# MCU_G0.net
KiCad netlist of a schematic drawn in Altium Designer
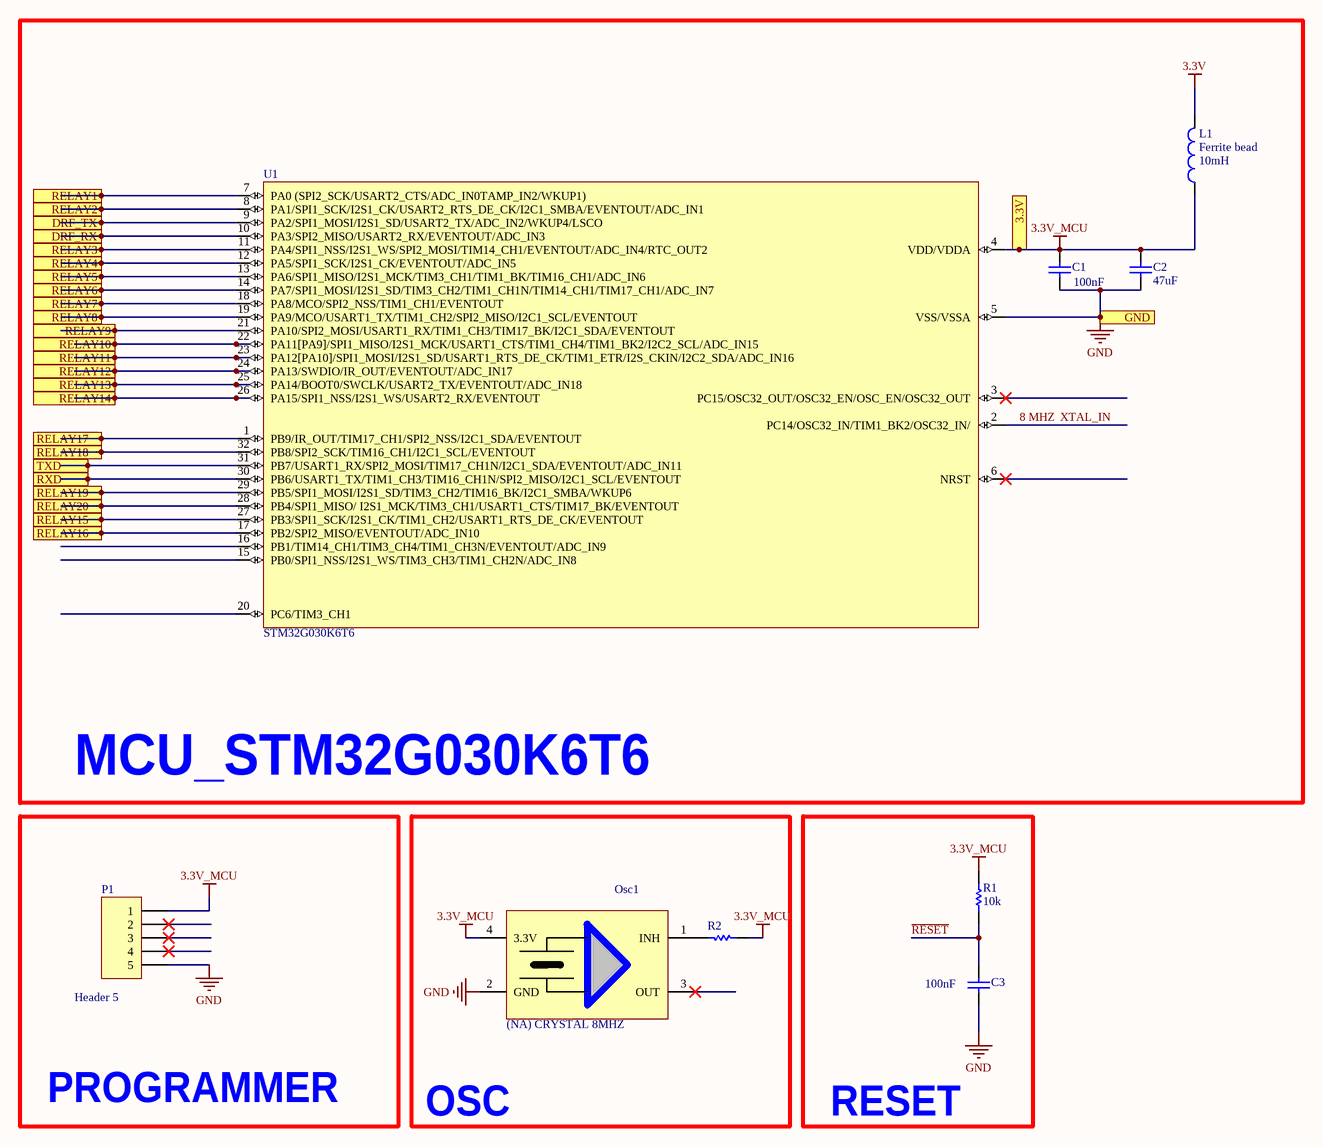
[diagram p0: MCU_G0.SchDoc]

(export (version "E")
  (design (tool "Eeschema 10.0.6"))
  (components
    (comp (ref "C1")
      (value "100nF")
      (footprint "0603 - RESISTOR")
      (description "Capacitor")
      (fields (field (name "PUBLISHER") "Altium Limited"))
      (libsource (lib "Miscellaneous Devices") (part "Cap"))
    )
    (comp (ref "C2")
      (value "47uF")
      (footprint "0603 - RESISTOR")
      (description "Capacitor")
      (fields (field (name "PUBLISHER") "Altium Limited"))
      (libsource (lib "Miscellaneous Devices") (part "Cap"))
    )
    (comp (ref "C3")
      (value "100nF")
      (footprint "0603 - RESISTOR")
      (description "Capacitor")
      (fields (field (name "PUBLISHER") "Altium Limited"))
      (libsource (lib "Miscellaneous Devices") (part "Cap"))
    )
    (comp (ref "L1")
      (value "Ferrite bead")
      (footprint "0603 - RESISTOR")
      (description "Inductor")
      (fields (field (name "ALTIUM_VALUE") "10mH") (field (name "PUBLISHER") "Altium Limited"))
      (libsource (lib "Miscellaneous Devices") (part "Inductor"))
    )
    (comp (ref "Osc1")
      (value "(NA) CRYSTAL 8MHZ")
      (footprint "XTAL_5X7")
      (libsource (lib "New Lib") (part "OSILATOR"))
    )
    (comp (ref "P1")
      (value "Header 5")
      (footprint "HDR1X5_2mm_small")
      (description "Header, 5-Pin")
      (fields (field (name "PUBLISHER") "Altium Limited"))
      (libsource (lib "Miscellaneous Connectors") (part "Header 5"))
    )
    (comp (ref "R1")
      (value "10k")
      (footprint "0603 - RESISTOR")
      (description "Resistor")
      (fields (field (name "PUBLISHER") "Altium Limited"))
      (libsource (lib "Miscellaneous Devices") (part "Res1"))
    )
    (comp (ref "R2")
      (value "(NA)10k")
      (footprint "0603 - RESISTOR")
      (description "Resistor")
      (fields (field (name "PUBLISHER") "Altium Limited"))
      (libsource (lib "Miscellaneous Devices") (part "Res1"))
    )
    (comp (ref "U1")
      (value "STM32G030K6T6")
      (footprint "LQFP32")
      (description "ARMÂ® CortexÂ®-M0+ STM32G0 Microcontroller IC 32-Bit 64MHz 32KB (32K x 8) FLASH 32-LQFP (7x7)")
      (fields (field (name "MF") "STMicroelectronics"))
      (libsource (lib "Schlib1") (part "STM32G030K6T6"))
    )
  )
  (nets
    (net (code "1") (name "/8 MHZ") (class "Default")
      (node (ref "U1") (pin "2") (pinfunction "PC14/OSC32_IN/TIM1_BK2/OSC32_IN/_2") (pintype "bidirectional"))
    )
    (net (code "2") (name "/DRF_RX") (class "Default")
      (node (ref "U1") (pin "10") (pinfunction "PA3/SPI2_MISO/USART2_RX/EVENTOUT/ADC_IN3_10") (pintype "bidirectional"))
    )
    (net (code "3") (name "/DRF_TX") (class "Default")
      (node (ref "U1") (pin "9") (pinfunction "PA2/SPI1_MOSI/I2S1_SD/USART2_TX/ADC_IN2/WKUP4/LSCO_9") (pintype "bidirectional"))
    )
    (net (code "4") (name "/RELAY1") (class "Default")
      (node (ref "U1") (pin "7") (pinfunction "PA0_(SPI2_SCK/USART2_CTS/ADC_IN0TAMP_IN2/WKUP1)_7") (pintype "bidirectional"))
    )
    (net (code "5") (name "/RELAY2") (class "Default")
      (node (ref "U1") (pin "8") (pinfunction "PA1/SPI1_SCK/I2S1_CK/USART2_RTS_DE_CK/I2C1_SMBA/EVENTOUT/ADC_IN1_8") (pintype "bidirectional"))
    )
    (net (code "6") (name "/RELAY3") (class "Default")
      (node (ref "U1") (pin "11") (pinfunction "PA4/SPI1_NSS/I2S1_WS/SPI2_MOSI/TIM14_CH1/EVENTOUT/ADC_IN4/RTC_OUT2_11") (pintype "bidirectional"))
    )
    (net (code "7") (name "/RELAY4") (class "Default")
      (node (ref "U1") (pin "12") (pinfunction "PA5/SPI1_SCK/I2S1_CK/EVENTOUT/ADC_IN5_12") (pintype "bidirectional"))
    )
    (net (code "8") (name "/RELAY5") (class "Default")
      (node (ref "U1") (pin "13") (pinfunction "PA6/SPI1_MISO/I2S1_MCK/TIM3_CH1/TIM1_BK/TIM16_CH1/ADC_IN6_13") (pintype "bidirectional"))
    )
    (net (code "9") (name "/RELAY6") (class "Default")
      (node (ref "U1") (pin "14") (pinfunction "PA7/SPI1_MOSI/I2S1_SD/TIM3_CH2/TIM1_CH1N/TIM14_CH1/TIM17_CH1/ADC_IN7_14") (pintype "bidirectional"))
    )
    (net (code "10") (name "/RELAY7") (class "Default")
      (node (ref "U1") (pin "18") (pinfunction "PA8/MCO/SPI2_NSS/TIM1_CH1/EVENTOUT_18") (pintype "bidirectional"))
    )
    (net (code "11") (name "/RELAY8") (class "Default")
      (node (ref "U1") (pin "19") (pinfunction "PA9/MCO/USART1_TX/TIM1_CH2/SPI2_MISO/I2C1_SCL/EVENTOUT_19") (pintype "bidirectional"))
    )
    (net (code "12") (name "/RELAY9") (class "Default")
      (node (ref "U1") (pin "21") (pinfunction "PA10/SPI2_MOSI/USART1_RX/TIM1_CH3/TIM17_BK/I2C1_SDA/EVENTOUT_21") (pintype "bidirectional"))
    )
    (net (code "13") (name "/RELAY10") (class "Default")
      (node (ref "U1") (pin "22") (pinfunction "PA11[PA9]/SPI1_MISO/I2S1_MCK/USART1_CTS/TIM1_CH4/TIM1_BK2/I2C2_SCL/ADC_IN15_22") (pintype "bidirectional"))
    )
    (net (code "14") (name "/RELAY11") (class "Default")
      (node (ref "U1") (pin "23") (pinfunction "PA12[PA10]/SPI1_MOSI/I2S1_SD/USART1_RTS_DE_CK/TIM1_ETR/I2S_CKIN/I2C2_SDA/ADC_IN16_23") (pintype "bidirectional"))
    )
    (net (code "15") (name "/RELAY12") (class "Default")
      (node (ref "U1") (pin "24") (pinfunction "PA13/SWDIO/IR_OUT/EVENTOUT/ADC_IN17_24") (pintype "bidirectional"))
    )
    (net (code "16") (name "/RELAY13") (class "Default")
      (node (ref "U1") (pin "25") (pinfunction "PA14/BOOT0/SWCLK/USART2_TX/EVENTOUT/ADC_IN18_25") (pintype "bidirectional"))
    )
    (net (code "17") (name "/RELAY14") (class "Default")
      (node (ref "U1") (pin "26") (pinfunction "PA15/SPI1_NSS/I2S1_WS/USART2_RX/EVENTOUT_26") (pintype "bidirectional"))
    )
    (net (code "18") (name "/RELAY15") (class "Default")
      (node (ref "U1") (pin "27") (pinfunction "PB3/SPI1_SCK/I2S1_CK/TIM1_CH2/USART1_RTS_DE_CK/EVENTOUT_27") (pintype "bidirectional"))
    )
    (net (code "19") (name "/RELAY16") (class "Default")
      (node (ref "U1") (pin "17") (pinfunction "PB2/SPI2_MISO/EVENTOUT/ADC_IN10_17") (pintype "bidirectional"))
    )
    (net (code "20") (name "/RELAY17") (class "Default")
      (node (ref "U1") (pin "1") (pinfunction "PB9/IR_OUT/TIM17_CH1/SPI2_NSS/I2C1_SDA/EVENTOUT_1") (pintype "bidirectional"))
    )
    (net (code "21") (name "/RELAY18") (class "Default")
      (node (ref "U1") (pin "32") (pinfunction "PB8/SPI2_SCK/TIM16_CH1/I2C1_SCL/EVENTOUT_32") (pintype "bidirectional"))
    )
    (net (code "22") (name "/RELAY19") (class "Default")
      (node (ref "U1") (pin "29") (pinfunction "PB5/SPI1_MOSI/I2S1_SD/TIM3_CH2/TIM16_BK/I2C1_SMBA/WKUP6_29") (pintype "bidirectional"))
    )
    (net (code "23") (name "/RELAY20") (class "Default")
      (node (ref "U1") (pin "28") (pinfunction "PB4/SPI1_MISO/_I2S1_MCK/TIM3_CH1/USART1_CTS/TIM17_BK/EVENTOUT_28") (pintype "bidirectional"))
    )
    (net (code "24") (name "/RXD") (class "Default")
      (node (ref "U1") (pin "30") (pinfunction "PB6/USART1_TX/TIM1_CH3/TIM16_CH1N/SPI2_MISO/I2C1_SCL/EVENTOUT_30") (pintype "bidirectional"))
    )
    (net (code "25") (name "/TXD") (class "Default")
      (node (ref "U1") (pin "31") (pinfunction "PB7/USART1_RX/SPI2_MOSI/TIM17_CH1N/I2C1_SDA/EVENTOUT/ADC_IN11_31") (pintype "bidirectional"))
    )
    (net (code "26") (name "/~{RESET}") (class "Default")
      (node (ref "C3") (pin "2") (pinfunction "2_2") (pintype "passive"))
      (node (ref "R1") (pin "1") (pinfunction "1_1") (pintype "passive"))
    )
    (net (code "27") (name "3.3V") (class "Default")
      (node (ref "C1") (pin "2") (pinfunction "2_2") (pintype "passive"))
      (node (ref "C2") (pin "2") (pinfunction "2_2") (pintype "passive"))
      (node (ref "L1") (pin "1") (pinfunction "1_1") (pintype "passive"))
      (node (ref "L1") (pin "2") (pinfunction "2_2") (pintype "passive"))
      (node (ref "Osc1") (pin "4") (pinfunction "3.3V_4") (pintype "passive"))
      (node (ref "P1") (pin "1") (pinfunction "1_1") (pintype "passive"))
      (node (ref "R1") (pin "2") (pinfunction "2_2") (pintype "passive"))
      (node (ref "R2") (pin "1") (pinfunction "1_1") (pintype "passive"))
      (node (ref "U1") (pin "4") (pinfunction "VDD/VDDA_4") (pintype "bidirectional"))
    )
    (net (code "28") (name "GND") (class "Default")
      (node (ref "C1") (pin "1") (pinfunction "1_1") (pintype "passive"))
      (node (ref "C2") (pin "1") (pinfunction "1_1") (pintype "passive"))
      (node (ref "C3") (pin "1") (pinfunction "1_1") (pintype "passive"))
      (node (ref "Osc1") (pin "2") (pinfunction "GND_2") (pintype "passive"))
      (node (ref "P1") (pin "5") (pinfunction "5_5") (pintype "passive"))
      (node (ref "U1") (pin "5") (pinfunction "VSS/VSSA_5") (pintype "bidirectional"))
    )
    (net (code "29") (name "Net-(Osc1-INH)") (class "Default")
      (node (ref "Osc1") (pin "1") (pinfunction "INH_1") (pintype "passive"))
      (node (ref "R2") (pin "2") (pinfunction "2_2") (pintype "passive"))
    )
    (net (code "30") (name "unconnected-(Osc1-OUT-Pad3)") (class "Default")
      (node (ref "Osc1") (pin "3") (pinfunction "OUT_3") (pintype "passive+no_connect"))
    )
    (net (code "31") (name "unconnected-(P1-Pad2)") (class "Default")
      (node (ref "P1") (pin "2") (pinfunction "2_2") (pintype "passive+no_connect"))
    )
    (net (code "32") (name "unconnected-(P1-Pad3)") (class "Default")
      (node (ref "P1") (pin "3") (pinfunction "3_3") (pintype "passive+no_connect"))
    )
    (net (code "33") (name "unconnected-(P1-Pad4)") (class "Default")
      (node (ref "P1") (pin "4") (pinfunction "4_4") (pintype "passive+no_connect"))
    )
    (net (code "34") (name "unconnected-(U1-NRST-Pad6)") (class "Default")
      (node (ref "U1") (pin "6") (pinfunction "NRST_6") (pintype "bidirectional+no_connect"))
    )
    (net (code "35") (name "unconnected-(U1-PB0{slash}SPI1_NSS{slash}I2S1_WS{slash}TIM3_CH3{slash}TIM1_CH2N{slash}ADC_IN8-Pad15)") (class "Default")
      (node (ref "U1") (pin "15") (pinfunction "PB0/SPI1_NSS/I2S1_WS/TIM3_CH3/TIM1_CH2N/ADC_IN8_15") (pintype "bidirectional"))
    )
    (net (code "36") (name "unconnected-(U1-PB1{slash}TIM14_CH1{slash}TIM3_CH4{slash}TIM1_CH3N{slash}EVENTOUT{slash}ADC_IN9-Pad16)") (class "Default")
      (node (ref "U1") (pin "16") (pinfunction "PB1/TIM14_CH1/TIM3_CH4/TIM1_CH3N/EVENTOUT/ADC_IN9_16") (pintype "bidirectional"))
    )
    (net (code "37") (name "unconnected-(U1-PC6{slash}TIM3_CH1-Pad20)") (class "Default")
      (node (ref "U1") (pin "20") (pinfunction "PC6/TIM3_CH1_20") (pintype "bidirectional"))
    )
    (net (code "38") (name "unconnected-(U1-PC15{slash}OSC32_OUT{slash}OSC32_EN{slash}OSC_EN{slash}OSC32_OUT-Pad3)") (class "Default")
      (node (ref "U1") (pin "3") (pinfunction "PC15/OSC32_OUT/OSC32_EN/OSC_EN/OSC32_OUT_3") (pintype "bidirectional+no_connect"))
    )
  )
)
